# Accessory_Breakout_X1.net
KiCad netlist of a schematic drawn in Altium Designer
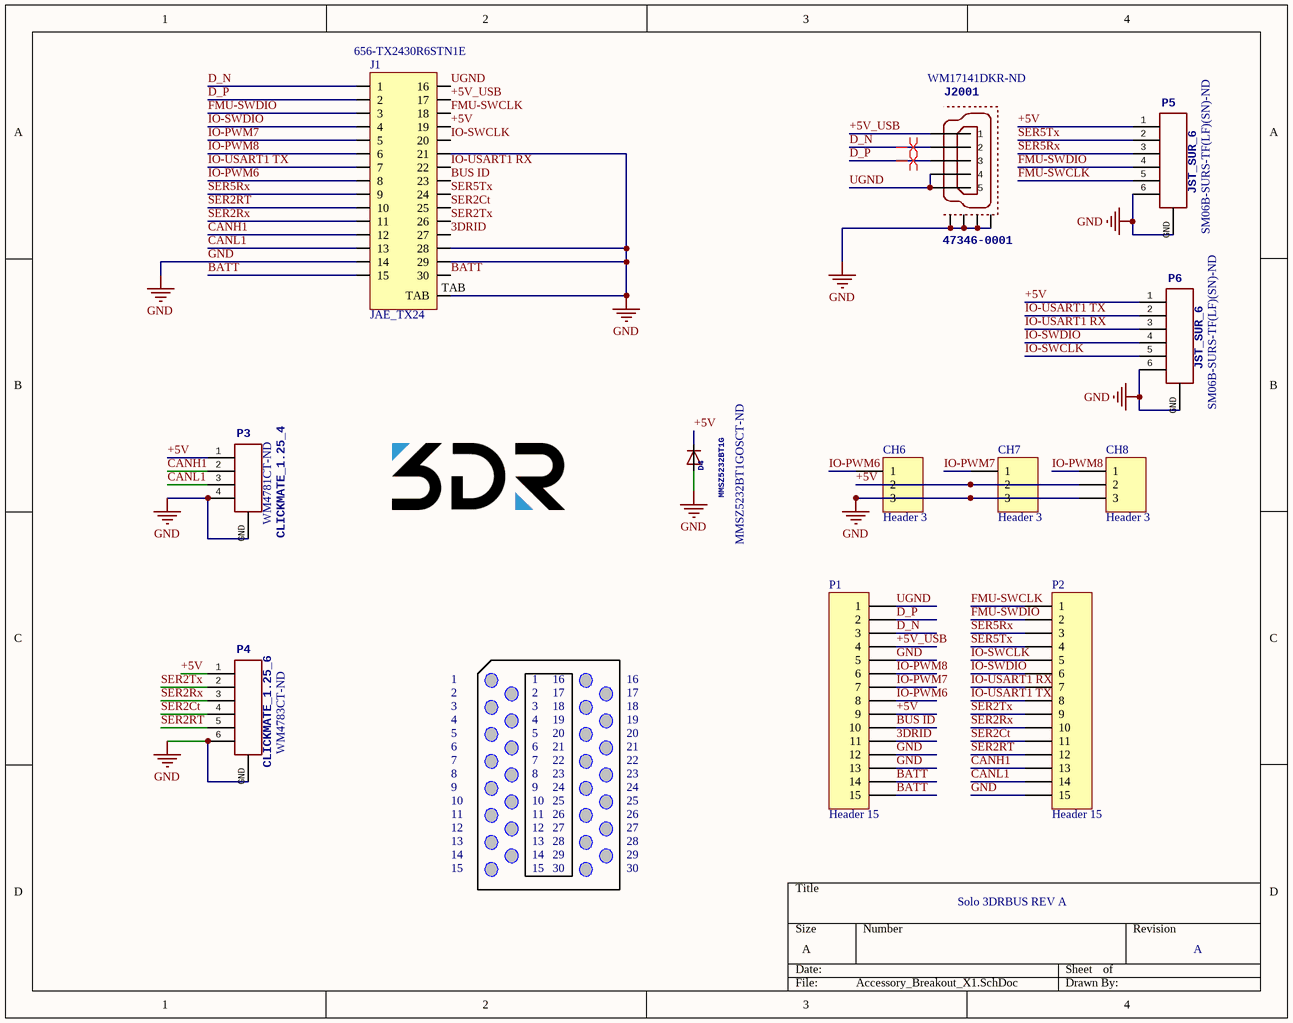
[diagram p0: Accessory_Breakout_X1.SchDoc]

(export (version "E")
  (design (tool "Eeschema 10.0.6"))
  (components
    (comp (ref "3DR Logo")
      (value "DO NOT PLACE")
      (footprint "3DR_Large")
      (libsource (lib "3DR") (part "3DR_LOGO"))
    )
    (comp (ref "CH6")
      (value "Header 3")
      (footprint "HDR1X3")
      (description "Header, 3-Pin")
      (fields (field (name "PUBLISHER") "Altium Limited"))
      (libsource (lib "Miscellaneous Connectors") (part "Header 3"))
    )
    (comp (ref "CH7")
      (value "Header 3")
      (footprint "HDR1X3")
      (description "Header, 3-Pin")
      (fields (field (name "PUBLISHER") "Altium Limited"))
      (libsource (lib "Miscellaneous Connectors") (part "Header 3"))
    )
    (comp (ref "CH8")
      (value "Header 3")
      (footprint "HDR1X3")
      (description "Header, 3-Pin")
      (fields (field (name "PUBLISHER") "Altium Limited"))
      (libsource (lib "Miscellaneous Connectors") (part "Header 3"))
    )
    (comp (ref "D4")
      (value "MMSZ5232BT1G")
      (footprint "SOD-123")
      (description "DIODE ZENER 5.6V 500MW SOD123")
      (fields
        (field (name "SUPPLIER PART NUMBER 1") "MMSZ5232BT1GOSCT-ND")
        (field (name "3DR_PARTNO") "ECM0536")
      )
      (libsource (lib "adafruit") (part "DIODESOD-123"))
    )
    (comp (ref "J1")
      (value "JAE_TX24")
      (footprint "JAE TX24")
      (fields (field (name "SUPPLIER PART NUMBER 1") "656-TX2430R6STN1E"))
      (libsource (lib "3DR") (part "JAE_TX24"))
    )
    (comp (ref "J2001")
      (value "47346-0001")
      (footprint "MOLEX-47346-0001")
      (description "MICRO USB B, BOTTOM MOUNT")
      (fields
        (field (name "SUPPLIER PART NUMBER 1") "WM17141DKR-ND")
        (field (name "3DR_PARTNO") "ECM0486")
        (field (name "PARTNO") "0473460001")
      )
      (libsource (lib "pixhawk2") (part "MOLEX-47346-0001"))
    )
    (comp (ref "P1")
      (value "Header 15")
      (footprint "HDR1X15")
      (description "Header, 15-Pin")
      (fields (field (name "PUBLISHER") "Altium Limited"))
      (libsource (lib "") (part "Header 15_1"))
    )
    (comp (ref "P2")
      (value "Header 15")
      (footprint "HDR1X15")
      (description "Header, 15-Pin")
      (fields (field (name "PUBLISHER") "Altium Limited"))
      (libsource (lib "Miscellaneous Connectors") (part "Header 15"))
    )
    (comp (ref "P3")
      (value "CLICKMATE_1.25_4")
      (footprint "CLICKMATE_V4")
      (description "Connector, Rcpt, 4Pos, 1.25MM, W/B, VERT, SMD, Tin")
      (fields (field (name "SUPPLIER PART NUMBER 1") "WM4781CT-ND") (field (name "3DR_PARTNO") "PRT0441"))
      (libsource (lib "PCA_0005_FULL_CB_REV_A") (part "CLICKMATE_1.25_4"))
    )
    (comp (ref "P4")
      (value "CLICKMATE_1.25_6")
      (footprint "CLICKMATE_V6")
      (description "Connector, Rcpt, 6Pos, 1.25MM, W/B, VERT, SMD, Tin")
      (fields (field (name "SUPPLIER PART NUMBER 1") "WM4783CT-ND") (field (name "3DR_PARTNO") "PRT0439"))
      (libsource (lib "PCA_0005_FULL_CB_REV_A") (part "CLICKMATE_1.25_6"))
    )
    (comp (ref "P5")
      (value "JST_SUR_6")
      (footprint "JST_SUR_H6")
      (description "Connector, Header, 6Pos, .8mm IDC, R/A, SMD, Tin")
      (fields
        (field (name "SUPPLIER PART NUMBER 1") "SM06B-SURS-TF(LF)(SN)-ND")
        (field (name "3DR_PARTNO") "PRT0442")
      )
      (libsource (lib "PCA_0005_FULL_CB_REV_A") (part "JST_SUR_6"))
    )
    (comp (ref "P6")
      (value "JST_SUR_6")
      (footprint "JST_SUR_H6")
      (description "Connector, Header, 6Pos, .8mm IDC, R/A, SMD, Tin")
      (fields
        (field (name "SUPPLIER PART NUMBER 1") "SM06B-SURS-TF(LF)(SN)-ND")
        (field (name "3DR_PARTNO") "PRT0442")
      )
      (libsource (lib "PCA_0005_FULL_CB_REV_A") (part "JST_SUR_6"))
    )
  )
  (nets
    (net (code "1") (name "/+5V") (class "Default")
      (node (ref "CH6") (pin "2") (pinfunction "2_2") (pintype "passive"))
      (node (ref "CH7") (pin "2") (pinfunction "2_2") (pintype "passive"))
      (node (ref "CH8") (pin "2") (pinfunction "2_2") (pintype "passive"))
      (node (ref "D4") (pin "C") (pinfunction "C_C") (pintype "passive"))
      (node (ref "J1") (pin "19") (pinfunction "19_19") (pintype "passive"))
      (node (ref "P1") (pin "9") (pinfunction "9_9") (pintype "passive"))
      (node (ref "P3") (pin "1") (pinfunction "1_1") (pintype "passive"))
      (node (ref "P4") (pin "1") (pinfunction "1_1") (pintype "passive"))
      (node (ref "P5") (pin "1") (pinfunction "1_1") (pintype "passive"))
      (node (ref "P6") (pin "1") (pinfunction "1_1") (pintype "passive"))
    )
    (net (code "2") (name "/+5V_USB") (class "Default")
      (node (ref "J1") (pin "17") (pinfunction "17_17") (pintype "passive"))
      (node (ref "J2001") (pin "VBUS") (pinfunction "1_VBUS") (pintype "open_emitter"))
      (node (ref "P1") (pin "4") (pinfunction "4_4") (pintype "passive"))
    )
    (net (code "3") (name "/3DRID") (class "Default")
      (node (ref "J1") (pin "27") (pinfunction "27_27") (pintype "passive"))
      (node (ref "P1") (pin "11") (pinfunction "11_11") (pintype "passive"))
    )
    (net (code "4") (name "/BATT") (class "Default")
      (node (ref "J1") (pin "15") (pinfunction "15_15") (pintype "passive"))
      (node (ref "J1") (pin "30") (pinfunction "30_30") (pintype "passive"))
      (node (ref "P1") (pin "14") (pinfunction "14_14") (pintype "passive"))
      (node (ref "P1") (pin "15") (pinfunction "15_15") (pintype "passive"))
    )
    (net (code "5") (name "/BUS ID") (class "Default")
      (node (ref "J1") (pin "23") (pinfunction "23_23") (pintype "passive"))
      (node (ref "P1") (pin "10") (pinfunction "10_10") (pintype "passive"))
    )
    (net (code "6") (name "/CANH1") (class "Default")
      (node (ref "J1") (pin "12") (pinfunction "12_12") (pintype "passive"))
      (node (ref "P2") (pin "13") (pinfunction "13_13") (pintype "passive"))
      (node (ref "P3") (pin "2") (pinfunction "2_2") (pintype "passive"))
    )
    (net (code "7") (name "/CANL1") (class "Default")
      (node (ref "J1") (pin "13") (pinfunction "13_13") (pintype "passive"))
      (node (ref "P2") (pin "14") (pinfunction "14_14") (pintype "passive"))
      (node (ref "P3") (pin "3") (pinfunction "3_3") (pintype "passive"))
    )
    (net (code "8") (name "/D_N") (class "Default")
      (node (ref "J1") (pin "1") (pinfunction "1_1") (pintype "passive"))
      (node (ref "J2001") (pin "D-") (pinfunction "2_D-") (pintype "passive"))
      (node (ref "P1") (pin "3") (pinfunction "3_3") (pintype "passive"))
    )
    (net (code "9") (name "/D_P") (class "Default")
      (node (ref "J1") (pin "2") (pinfunction "2_2") (pintype "passive"))
      (node (ref "J2001") (pin "D+") (pinfunction "3_D+") (pintype "passive"))
      (node (ref "P1") (pin "2") (pinfunction "2_2") (pintype "passive"))
    )
    (net (code "10") (name "/FMU-SWCLK") (class "Default")
      (node (ref "J1") (pin "18") (pinfunction "18_18") (pintype "passive"))
      (node (ref "P2") (pin "1") (pinfunction "1_1") (pintype "passive"))
      (node (ref "P5") (pin "5") (pinfunction "5_5") (pintype "passive"))
    )
    (net (code "11") (name "/FMU-SWDIO") (class "Default")
      (node (ref "J1") (pin "3") (pinfunction "3_3") (pintype "passive"))
      (node (ref "P2") (pin "2") (pinfunction "2_2") (pintype "passive"))
      (node (ref "P5") (pin "4") (pinfunction "4_4") (pintype "passive"))
    )
    (net (code "12") (name "/IO-PWM6") (class "Default")
      (node (ref "CH6") (pin "1") (pinfunction "1_1") (pintype "passive"))
      (node (ref "J1") (pin "8") (pinfunction "8_8") (pintype "passive"))
      (node (ref "P1") (pin "8") (pinfunction "8_8") (pintype "passive"))
    )
    (net (code "13") (name "/IO-PWM7") (class "Default")
      (node (ref "CH7") (pin "1") (pinfunction "1_1") (pintype "passive"))
      (node (ref "J1") (pin "5") (pinfunction "5_5") (pintype "passive"))
      (node (ref "P1") (pin "7") (pinfunction "7_7") (pintype "passive"))
    )
    (net (code "14") (name "/IO-PWM8") (class "Default")
      (node (ref "CH8") (pin "1") (pinfunction "1_1") (pintype "passive"))
      (node (ref "J1") (pin "6") (pinfunction "6_6") (pintype "passive"))
      (node (ref "P1") (pin "6") (pinfunction "6_6") (pintype "passive"))
    )
    (net (code "15") (name "/IO-SWCLK") (class "Default")
      (node (ref "J1") (pin "20") (pinfunction "20_20") (pintype "passive"))
      (node (ref "P2") (pin "5") (pinfunction "5_5") (pintype "passive"))
      (node (ref "P6") (pin "5") (pinfunction "5_5") (pintype "passive"))
    )
    (net (code "16") (name "/IO-SWDIO") (class "Default")
      (node (ref "J1") (pin "4") (pinfunction "4_4") (pintype "passive"))
      (node (ref "P2") (pin "6") (pinfunction "6_6") (pintype "passive"))
      (node (ref "P6") (pin "4") (pinfunction "4_4") (pintype "passive"))
    )
    (net (code "17") (name "/IO-USART1 RX") (class "Default")
      (node (ref "J1") (pin "22") (pinfunction "22_22") (pintype "passive"))
      (node (ref "P2") (pin "7") (pinfunction "7_7") (pintype "passive"))
      (node (ref "P6") (pin "3") (pinfunction "3_3") (pintype "passive"))
    )
    (net (code "18") (name "/IO-USART1 TX") (class "Default")
      (node (ref "J1") (pin "7") (pinfunction "7_7") (pintype "passive"))
      (node (ref "P2") (pin "8") (pinfunction "8_8") (pintype "passive"))
      (node (ref "P6") (pin "2") (pinfunction "2_2") (pintype "passive"))
    )
    (net (code "19") (name "/SER2Ct") (class "Default")
      (node (ref "J1") (pin "25") (pinfunction "25_25") (pintype "passive"))
      (node (ref "P2") (pin "11") (pinfunction "11_11") (pintype "passive"))
      (node (ref "P4") (pin "4") (pinfunction "4_4") (pintype "passive"))
    )
    (net (code "20") (name "/SER2RT") (class "Default")
      (node (ref "J1") (pin "10") (pinfunction "10_10") (pintype "passive"))
      (node (ref "P2") (pin "12") (pinfunction "12_12") (pintype "passive"))
      (node (ref "P4") (pin "5") (pinfunction "5_5") (pintype "passive"))
    )
    (net (code "21") (name "/SER2Rx") (class "Default")
      (node (ref "J1") (pin "11") (pinfunction "11_11") (pintype "passive"))
      (node (ref "P2") (pin "10") (pinfunction "10_10") (pintype "passive"))
      (node (ref "P4") (pin "3") (pinfunction "3_3") (pintype "passive"))
    )
    (net (code "22") (name "/SER2Tx") (class "Default")
      (node (ref "J1") (pin "26") (pinfunction "26_26") (pintype "passive"))
      (node (ref "P2") (pin "9") (pinfunction "9_9") (pintype "passive"))
      (node (ref "P4") (pin "2") (pinfunction "2_2") (pintype "passive"))
    )
    (net (code "23") (name "/SER5Rx") (class "Default")
      (node (ref "J1") (pin "9") (pinfunction "9_9") (pintype "passive"))
      (node (ref "P2") (pin "3") (pinfunction "3_3") (pintype "passive"))
      (node (ref "P5") (pin "3") (pinfunction "3_3") (pintype "passive"))
    )
    (net (code "24") (name "/SER5Tx") (class "Default")
      (node (ref "J1") (pin "24") (pinfunction "24_24") (pintype "passive"))
      (node (ref "P2") (pin "4") (pinfunction "4_4") (pintype "passive"))
      (node (ref "P5") (pin "2") (pinfunction "2_2") (pintype "passive"))
    )
    (net (code "25") (name "/UGND") (class "Default")
      (node (ref "J1") (pin "16") (pinfunction "16_16") (pintype "passive"))
      (node (ref "J2001") (pin "GND") (pinfunction "5_GND") (pintype "open_emitter"))
      (node (ref "J2001") (pin "ID") (pinfunction "4_ID") (pintype "passive"))
      (node (ref "P1") (pin "1") (pinfunction "1_1") (pintype "passive"))
    )
    (net (code "26") (name "GND") (class "Default")
      (node (ref "CH6") (pin "3") (pinfunction "3_3") (pintype "passive"))
      (node (ref "CH7") (pin "3") (pinfunction "3_3") (pintype "passive"))
      (node (ref "CH8") (pin "3") (pinfunction "3_3") (pintype "passive"))
      (node (ref "D4") (pin "A") (pinfunction "A_A") (pintype "passive"))
      (node (ref "J1") (pin "14") (pinfunction "14_14") (pintype "passive"))
      (node (ref "J1") (pin "21") (pinfunction "21_21") (pintype "passive"))
      (node (ref "J1") (pin "28") (pinfunction "28_28") (pintype "passive"))
      (node (ref "J1") (pin "29") (pinfunction "29_29") (pintype "passive"))
      (node (ref "J1") (pin "TAB") (pinfunction "TAB_TAB") (pintype "passive"))
      (node (ref "J2001") (pin "GND1") (pinfunction "GND1_GND1") (pintype "passive"))
      (node (ref "J2001") (pin "GND2") (pinfunction "GND2_GND2") (pintype "passive"))
      (node (ref "J2001") (pin "GND3") (pinfunction "GND3_GND3") (pintype "passive"))
      (node (ref "J2001") (pin "GND4") (pinfunction "GND4_GND4") (pintype "passive"))
      (node (ref "P1") (pin "12") (pinfunction "12_12") (pintype "passive"))
      (node (ref "P1") (pin "13") (pinfunction "13_13") (pintype "passive"))
      (node (ref "P1") (pin "5") (pinfunction "5_5") (pintype "passive"))
      (node (ref "P2") (pin "15") (pinfunction "15_15") (pintype "passive"))
      (node (ref "P3") (pin "4") (pinfunction "4_4") (pintype "passive"))
      (node (ref "P3") (pin "GND") (pinfunction "GND_GND") (pintype "passive"))
      (node (ref "P4") (pin "6") (pinfunction "6_6") (pintype "passive"))
      (node (ref "P4") (pin "GND") (pinfunction "GND_GND") (pintype "passive"))
      (node (ref "P5") (pin "6") (pinfunction "6_6") (pintype "passive"))
      (node (ref "P5") (pin "GND") (pinfunction "GND_GND") (pintype "passive"))
      (node (ref "P6") (pin "6") (pinfunction "6_6") (pintype "passive"))
      (node (ref "P6") (pin "GND") (pinfunction "GND_GND") (pintype "passive"))
    )
  )
)
